# 555Oscillator.net
KiCad netlist of a schematic drawn in EAGLE
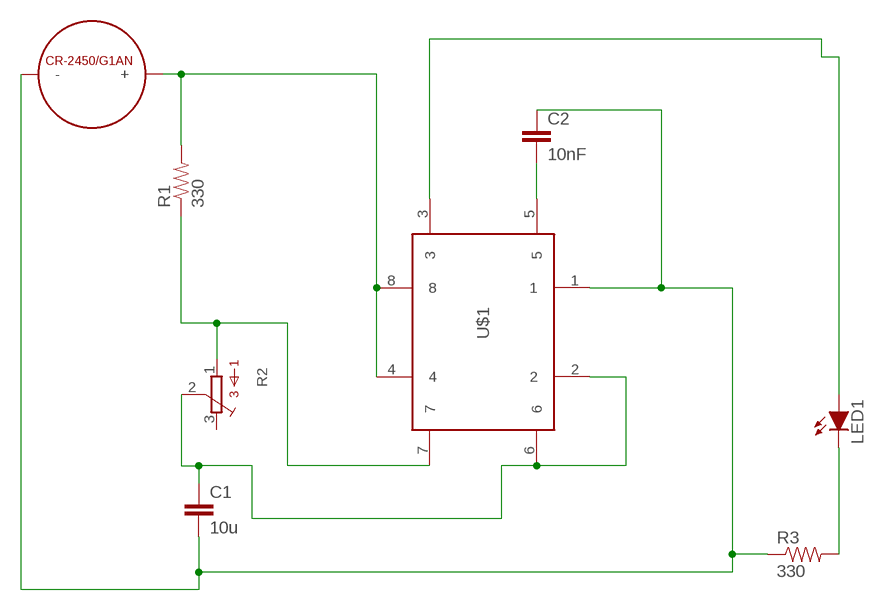
[diagram p0: schematic, sheet 1]

(export (version "E")
  (design (tool "Eeschema 10.0.6"))
  (components
    (comp (ref "C1")
      (value "10u")
      (footprint "eagle-import:AXIAL-5MM")
      (libsource (lib "eagle-import") (part "CAP_"))
    )
    (comp (ref "C2")
      (value "10nF")
      (footprint "eagle-import:AXIAL-5MM")
      (libsource (lib "eagle-import") (part "CAP_"))
    )
    (comp (ref "LED1")
      (value "LED-5MM")
      (footprint "eagle-import:LED-5MM")
      (libsource (lib "eagle-import") (part "LED-5MM"))
    )
    (comp (ref "R1")
      (value "330")
      (footprint "eagle-import:AXIAL-0.3")
      (libsource (lib "eagle-import") (part "RESISTORAXIAL-0.3"))
    )
    (comp (ref "R2")
      (value "TRIMPOT_3296C")
      (footprint "eagle-import:TRIMPOT_3296")
      (libsource (lib "eagle-import") (part "TRIMPOT_3296C"))
    )
    (comp (ref "R3")
      (value "330")
      (footprint "eagle-import:AXIAL-0.3")
      (libsource (lib "eagle-import") (part "RESISTORAXIAL-0.3"))
    )
    (comp (ref "U$1")
      (value "555_TIMER")
      (footprint "eagle-import:DIL08")
      (libsource (lib "eagle-import") (part "555_TIMER"))
    )
    (comp (ref "U$2")
      (value "CR-2450/G1AN")
      (footprint "eagle-import:CR-2450_G1AN")
      (libsource (lib "eagle-import") (part "CR-2450/G1AN"))
    )
  )
  (nets
    (net (code "1") (name "Net-(C1-1)") (class "Default")
      (node (ref "C1") (pin "P$1") (pinfunction "1_P$1") (pintype "passive"))
      (node (ref "R2") (pin "2") (pinfunction "2_2") (pintype "passive"))
      (node (ref "U$1") (pin "2") (pinfunction "2_2") (pintype "bidirectional"))
      (node (ref "U$1") (pin "6") (pinfunction "6_6") (pintype "bidirectional"))
    )
    (net (code "2") (name "Net-(C1-2)") (class "Default")
      (node (ref "C1") (pin "P$2") (pinfunction "2_P$2") (pintype "passive"))
      (node (ref "C2") (pin "P$1") (pinfunction "1_P$1") (pintype "passive"))
      (node (ref "R3") (pin "P$1") (pinfunction "1_P$1") (pintype "passive"))
      (node (ref "U$1") (pin "1") (pinfunction "1_1") (pintype "bidirectional"))
      (node (ref "U$2") (pin "-") (pinfunction "-_-") (pintype "bidirectional"))
    )
    (net (code "3") (name "Net-(C2-2)") (class "Default")
      (node (ref "C2") (pin "P$2") (pinfunction "2_P$2") (pintype "passive"))
      (node (ref "U$1") (pin "5") (pinfunction "5_5") (pintype "bidirectional"))
    )
    (net (code "4") (name "Net-(LED1-C)") (class "Default")
      (node (ref "LED1") (pin "K") (pinfunction "C_K") (pintype "passive"))
      (node (ref "R3") (pin "P$2") (pinfunction "2_P$2") (pintype "passive"))
    )
    (net (code "5") (name "Net-(LED1-PadA)") (class "Default")
      (node (ref "LED1") (pin "A") (pinfunction "A_A") (pintype "passive"))
      (node (ref "U$1") (pin "3") (pinfunction "3_3") (pintype "bidirectional"))
    )
    (net (code "6") (name "Net-(R1-1)") (class "Default")
      (node (ref "R1") (pin "P$1") (pinfunction "1_P$1") (pintype "passive"))
      (node (ref "R2") (pin "1") (pinfunction "1_1") (pintype "passive"))
      (node (ref "U$1") (pin "7") (pinfunction "7_7") (pintype "bidirectional"))
    )
    (net (code "7") (name "Net-(R1-2)") (class "Default")
      (node (ref "R1") (pin "P$2") (pinfunction "2_P$2") (pintype "passive"))
      (node (ref "U$1") (pin "4") (pinfunction "4_4") (pintype "bidirectional"))
      (node (ref "U$1") (pin "8") (pinfunction "8_8") (pintype "bidirectional"))
      (node (ref "U$2") (pin "+_0") (pinfunction "+_+_0") (pintype "bidirectional"))
      (node (ref "U$2") (pin "+_1") (pinfunction "+_+_1") (pintype "bidirectional"))
    )
    (net (code "8") (name "unconnected-(R2-Pad3)") (class "Default")
      (node (ref "R2") (pin "3") (pinfunction "3_3") (pintype "passive"))
    )
  )
)
